# TECLADO-G5-5A_schDoc.net
KiCad netlist of a schematic drawn in Altium Designer
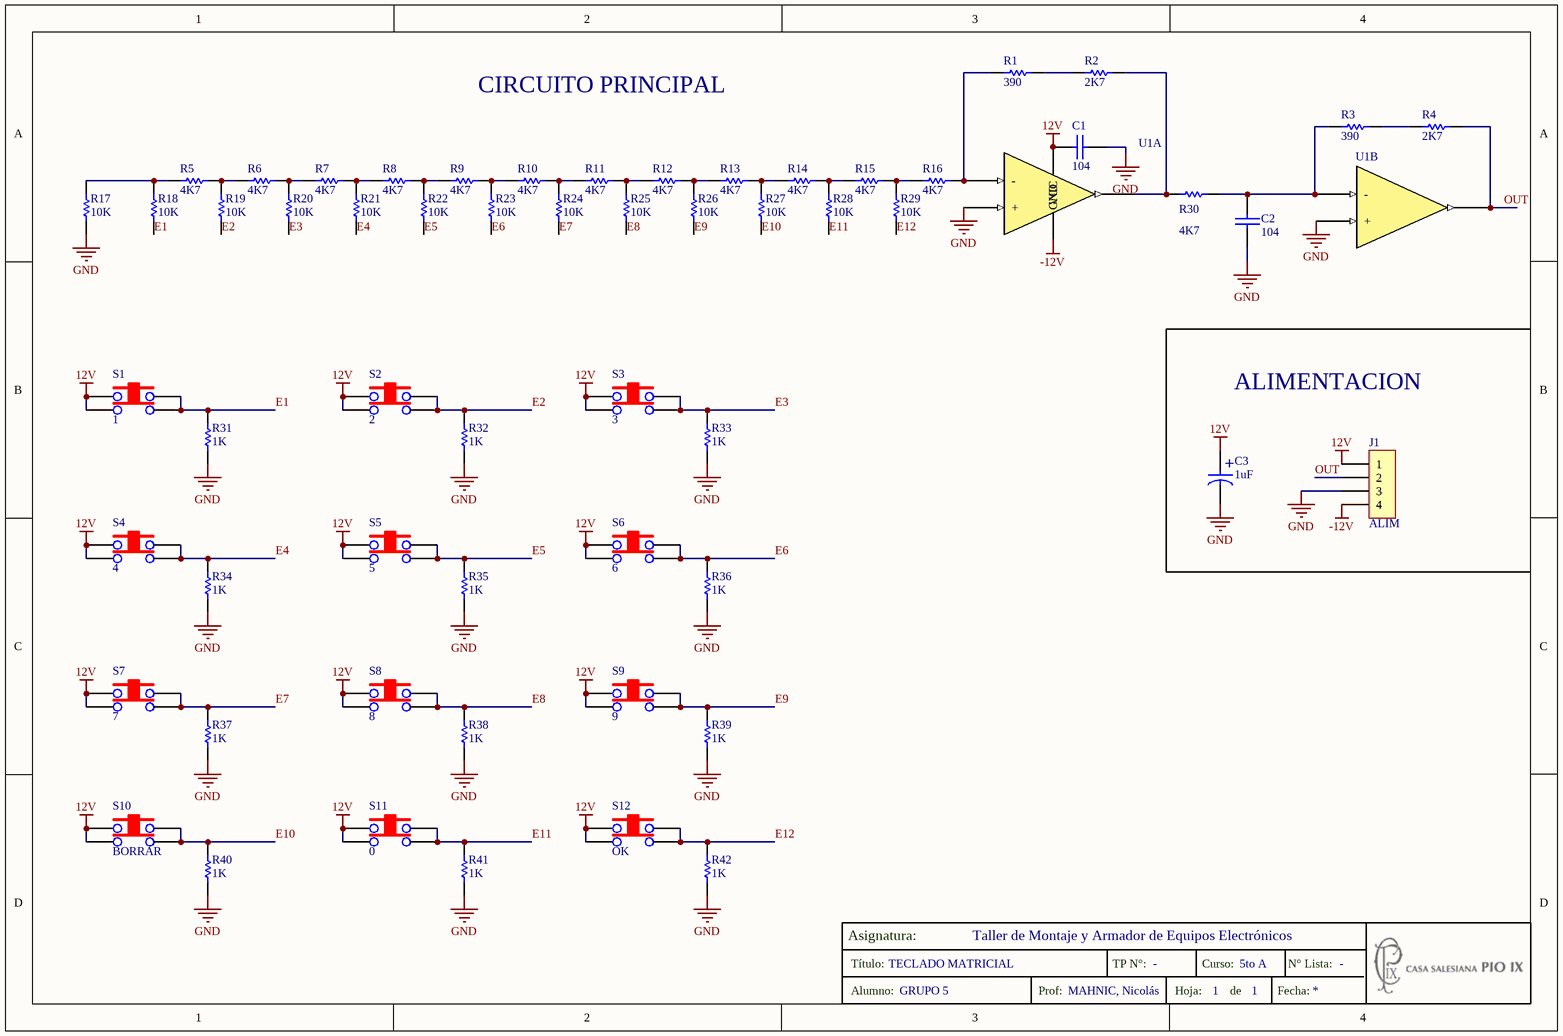
[diagram p0: TECLADO-G5-5A.schDoc.SchDoc]

(export (version "E")
  (design (tool "Eeschema 10.0.6"))
  (components
    (comp (ref "C1")
      (value "104")
      (footprint "0805")
      (description "Diodo 0805")
      (libsource (lib "Schlib1") (part "CAP"))
    )
    (comp (ref "C2")
      (value "104")
      (footprint "0805")
      (description "Diodo 0805")
      (libsource (lib "Schlib1") (part "CAP"))
    )
    (comp (ref "C3")
      (value "1uF")
      (footprint "Capol")
      (description "Cap polarizado")
      (libsource (lib "Schlib1") (part "CAPPOL"))
    )
    (comp (ref "J1") (value "ALIM") (footprint "SIP4") (libsource (lib "Schlib1") (part "CON4")))
    (comp (ref "R1")
      (value "390")
      (footprint "0805")
      (description "Resistencia")
      (libsource (lib "Schlib1") (part "RES"))
    )
    (comp (ref "R2")
      (value "2K7")
      (footprint "0805")
      (description "Resistencia")
      (libsource (lib "Schlib1") (part "RES"))
    )
    (comp (ref "R3")
      (value "390")
      (footprint "0805")
      (description "Resistencia")
      (libsource (lib "Schlib1") (part "RES"))
    )
    (comp (ref "R4")
      (value "2K7")
      (footprint "0805")
      (description "Resistencia")
      (libsource (lib "Schlib1") (part "RES"))
    )
    (comp (ref "R5")
      (value "4K7")
      (footprint "0805")
      (description "Resistencia")
      (libsource (lib "Schlib1") (part "RES"))
    )
    (comp (ref "R6")
      (value "4K7")
      (footprint "0805")
      (description "Resistencia")
      (libsource (lib "Schlib1") (part "RES"))
    )
    (comp (ref "R7")
      (value "4K7")
      (footprint "0805")
      (description "Resistencia")
      (libsource (lib "Schlib1") (part "RES"))
    )
    (comp (ref "R8")
      (value "4K7")
      (footprint "0805")
      (description "Resistencia")
      (libsource (lib "Schlib1") (part "RES"))
    )
    (comp (ref "R9")
      (value "4K7")
      (footprint "0805")
      (description "Resistencia")
      (libsource (lib "Schlib1") (part "RES"))
    )
    (comp (ref "R10")
      (value "4K7")
      (footprint "0805")
      (description "Resistencia")
      (libsource (lib "Schlib1") (part "RES"))
    )
    (comp (ref "R11")
      (value "4K7")
      (footprint "0805")
      (description "Resistencia")
      (libsource (lib "Schlib1") (part "RES"))
    )
    (comp (ref "R12")
      (value "4K7")
      (footprint "0805")
      (description "Resistencia")
      (libsource (lib "Schlib1") (part "RES"))
    )
    (comp (ref "R13")
      (value "4K7")
      (footprint "0805")
      (description "Resistencia")
      (libsource (lib "Schlib1") (part "RES"))
    )
    (comp (ref "R14")
      (value "4K7")
      (footprint "0805")
      (description "Resistencia")
      (libsource (lib "Schlib1") (part "RES"))
    )
    (comp (ref "R15")
      (value "4K7")
      (footprint "0805")
      (description "Resistencia")
      (libsource (lib "Schlib1") (part "RES"))
    )
    (comp (ref "R16")
      (value "4K7")
      (footprint "0805")
      (description "Resistencia")
      (libsource (lib "Schlib1") (part "RES"))
    )
    (comp (ref "R17")
      (value "10K")
      (footprint "0805")
      (description "Resistencia")
      (libsource (lib "Schlib1") (part "RES"))
    )
    (comp (ref "R18")
      (value "10K")
      (footprint "0805")
      (description "Resistencia")
      (libsource (lib "Schlib1") (part "RES"))
    )
    (comp (ref "R19")
      (value "10K")
      (footprint "0805")
      (description "Resistencia")
      (libsource (lib "Schlib1") (part "RES"))
    )
    (comp (ref "R20")
      (value "10K")
      (footprint "0805")
      (description "Resistencia")
      (libsource (lib "Schlib1") (part "RES"))
    )
    (comp (ref "R21")
      (value "10K")
      (footprint "0805")
      (description "Resistencia")
      (libsource (lib "Schlib1") (part "RES"))
    )
    (comp (ref "R22")
      (value "10K")
      (footprint "0805")
      (description "Resistencia")
      (libsource (lib "Schlib1") (part "RES"))
    )
    (comp (ref "R23")
      (value "10K")
      (footprint "0805")
      (description "Resistencia")
      (libsource (lib "Schlib1") (part "RES"))
    )
    (comp (ref "R24")
      (value "10K")
      (footprint "0805")
      (description "Resistencia")
      (libsource (lib "Schlib1") (part "RES"))
    )
    (comp (ref "R25")
      (value "10K")
      (footprint "0805")
      (description "Resistencia")
      (libsource (lib "Schlib1") (part "RES"))
    )
    (comp (ref "R26")
      (value "10K")
      (footprint "0805")
      (description "Resistencia")
      (libsource (lib "Schlib1") (part "RES"))
    )
    (comp (ref "R27")
      (value "10K")
      (footprint "0805")
      (description "Resistencia")
      (libsource (lib "Schlib1") (part "RES"))
    )
    (comp (ref "R28")
      (value "10K")
      (footprint "0805")
      (description "Resistencia")
      (libsource (lib "Schlib1") (part "RES"))
    )
    (comp (ref "R29")
      (value "10K")
      (footprint "0805")
      (description "Resistencia")
      (libsource (lib "Schlib1") (part "RES"))
    )
    (comp (ref "R30")
      (value "4K7")
      (footprint "0805")
      (description "Resistencia")
      (libsource (lib "Schlib1") (part "RES"))
    )
    (comp (ref "R31")
      (value "1K")
      (footprint "0805")
      (description "Resistencia")
      (libsource (lib "Schlib1") (part "RES"))
    )
    (comp (ref "R32")
      (value "1K")
      (footprint "0805")
      (description "Resistencia")
      (libsource (lib "Schlib1") (part "RES"))
    )
    (comp (ref "R33")
      (value "1K")
      (footprint "0805")
      (description "Resistencia")
      (libsource (lib "Schlib1") (part "RES"))
    )
    (comp (ref "R34")
      (value "1K")
      (footprint "0805")
      (description "Resistencia")
      (libsource (lib "Schlib1") (part "RES"))
    )
    (comp (ref "R35")
      (value "1K")
      (footprint "0805")
      (description "Resistencia")
      (libsource (lib "Schlib1") (part "RES"))
    )
    (comp (ref "R36")
      (value "1K")
      (footprint "0805")
      (description "Resistencia")
      (libsource (lib "Schlib1") (part "RES"))
    )
    (comp (ref "R37")
      (value "1K")
      (footprint "0805")
      (description "Resistencia")
      (libsource (lib "Schlib1") (part "RES"))
    )
    (comp (ref "R38")
      (value "1K")
      (footprint "0805")
      (description "Resistencia")
      (libsource (lib "Schlib1") (part "RES"))
    )
    (comp (ref "R39")
      (value "1K")
      (footprint "0805")
      (description "Resistencia")
      (libsource (lib "Schlib1") (part "RES"))
    )
    (comp (ref "R40")
      (value "1K")
      (footprint "0805")
      (description "Resistencia")
      (libsource (lib "Schlib1") (part "RES"))
    )
    (comp (ref "R41")
      (value "1K")
      (footprint "0805")
      (description "Resistencia")
      (libsource (lib "Schlib1") (part "RES"))
    )
    (comp (ref "R42")
      (value "1K")
      (footprint "0805")
      (description "Resistencia")
      (libsource (lib "Schlib1") (part "RES"))
    )
    (comp (ref "S1")
      (value "1")
      (footprint "pul_grande")
      (description "Pulsador")
      (fields (field (name "AUTOR") "Guido Spataro"))
      (libsource (lib "Schlib1") (part "Pulsador"))
    )
    (comp (ref "S2")
      (value "2")
      (footprint "pul_grande")
      (description "Pulsador")
      (fields (field (name "AUTOR") "Guido Spataro"))
      (libsource (lib "Schlib1") (part "Pulsador"))
    )
    (comp (ref "S3")
      (value "3")
      (footprint "pul_grande")
      (description "Pulsador")
      (fields (field (name "AUTOR") "Guido Spataro"))
      (libsource (lib "Schlib1") (part "Pulsador"))
    )
    (comp (ref "S4")
      (value "4")
      (footprint "pul_grande")
      (description "Pulsador")
      (fields (field (name "AUTOR") "Guido Spataro"))
      (libsource (lib "Schlib1") (part "Pulsador"))
    )
    (comp (ref "S5")
      (value "5")
      (footprint "pul_grande")
      (description "Pulsador")
      (fields (field (name "AUTOR") "Guido Spataro"))
      (libsource (lib "Schlib1") (part "Pulsador"))
    )
    (comp (ref "S6")
      (value "6")
      (footprint "pul_grande")
      (description "Pulsador")
      (fields (field (name "AUTOR") "Guido Spataro"))
      (libsource (lib "Schlib1") (part "Pulsador"))
    )
    (comp (ref "S7")
      (value "7")
      (footprint "pul_grande")
      (description "Pulsador")
      (fields (field (name "AUTOR") "Guido Spataro"))
      (libsource (lib "Schlib1") (part "Pulsador"))
    )
    (comp (ref "S8")
      (value "8")
      (footprint "pul_grande")
      (description "Pulsador")
      (fields (field (name "AUTOR") "Guido Spataro"))
      (libsource (lib "Schlib1") (part "Pulsador"))
    )
    (comp (ref "S9")
      (value "9")
      (footprint "pul_grande")
      (description "Pulsador")
      (fields (field (name "AUTOR") "Guido Spataro"))
      (libsource (lib "Schlib1") (part "Pulsador"))
    )
    (comp (ref "S10")
      (value "BORRAR")
      (footprint "pul_grande")
      (description "Pulsador")
      (fields (field (name "AUTOR") "Guido Spataro"))
      (libsource (lib "Schlib1") (part "Pulsador"))
    )
    (comp (ref "S11")
      (value "0")
      (footprint "pul_grande")
      (description "Pulsador")
      (fields (field (name "AUTOR") "Guido Spataro"))
      (libsource (lib "Schlib1") (part "Pulsador"))
    )
    (comp (ref "S12")
      (value "OK")
      (footprint "pul_grande")
      (description "Pulsador")
      (fields (field (name "AUTOR") "Guido Spataro"))
      (libsource (lib "Schlib1") (part "Pulsador"))
    )
    (comp (ref "U1") (value "~") (footprint "LM358 SMD") (libsource (lib "Schlib1") (part "LM358")))
  )
  (nets
    (net (code "1") (name "-12V") (class "Default")
      (node (ref "J1") (pin "4") (pinfunction "4_4") (pintype "passive"))
      (node (ref "U1") (pin "4") (pinfunction "GND_4") (pintype "passive"))
    )
    (net (code "2") (name "/E1") (class "Default")
      (node (ref "R18") (pin "1") (pinfunction "1_1") (pintype "passive"))
      (node (ref "R31") (pin "2") (pinfunction "2_2") (pintype "passive"))
      (node (ref "S1") (pin "3") (pinfunction "3_3") (pintype "passive"))
      (node (ref "S1") (pin "4") (pinfunction "4_4") (pintype "passive"))
    )
    (net (code "3") (name "/E2") (class "Default")
      (node (ref "R19") (pin "1") (pinfunction "1_1") (pintype "passive"))
      (node (ref "R32") (pin "2") (pinfunction "2_2") (pintype "passive"))
      (node (ref "S2") (pin "3") (pinfunction "3_3") (pintype "passive"))
      (node (ref "S2") (pin "4") (pinfunction "4_4") (pintype "passive"))
    )
    (net (code "4") (name "/E3") (class "Default")
      (node (ref "R20") (pin "1") (pinfunction "1_1") (pintype "passive"))
      (node (ref "R33") (pin "2") (pinfunction "2_2") (pintype "passive"))
      (node (ref "S3") (pin "3") (pinfunction "3_3") (pintype "passive"))
      (node (ref "S3") (pin "4") (pinfunction "4_4") (pintype "passive"))
    )
    (net (code "5") (name "/E4") (class "Default")
      (node (ref "R21") (pin "1") (pinfunction "1_1") (pintype "passive"))
      (node (ref "R34") (pin "2") (pinfunction "2_2") (pintype "passive"))
      (node (ref "S4") (pin "3") (pinfunction "3_3") (pintype "passive"))
      (node (ref "S4") (pin "4") (pinfunction "4_4") (pintype "passive"))
    )
    (net (code "6") (name "/E5") (class "Default")
      (node (ref "R22") (pin "1") (pinfunction "1_1") (pintype "passive"))
      (node (ref "R35") (pin "2") (pinfunction "2_2") (pintype "passive"))
      (node (ref "S5") (pin "3") (pinfunction "3_3") (pintype "passive"))
      (node (ref "S5") (pin "4") (pinfunction "4_4") (pintype "passive"))
    )
    (net (code "7") (name "/E6") (class "Default")
      (node (ref "R23") (pin "1") (pinfunction "1_1") (pintype "passive"))
      (node (ref "R36") (pin "2") (pinfunction "2_2") (pintype "passive"))
      (node (ref "S6") (pin "3") (pinfunction "3_3") (pintype "passive"))
      (node (ref "S6") (pin "4") (pinfunction "4_4") (pintype "passive"))
    )
    (net (code "8") (name "/E7") (class "Default")
      (node (ref "R24") (pin "1") (pinfunction "1_1") (pintype "passive"))
      (node (ref "R37") (pin "2") (pinfunction "2_2") (pintype "passive"))
      (node (ref "S7") (pin "3") (pinfunction "3_3") (pintype "passive"))
      (node (ref "S7") (pin "4") (pinfunction "4_4") (pintype "passive"))
    )
    (net (code "9") (name "/E8") (class "Default")
      (node (ref "R25") (pin "1") (pinfunction "1_1") (pintype "passive"))
      (node (ref "R38") (pin "2") (pinfunction "2_2") (pintype "passive"))
      (node (ref "S8") (pin "3") (pinfunction "3_3") (pintype "passive"))
      (node (ref "S8") (pin "4") (pinfunction "4_4") (pintype "passive"))
    )
    (net (code "10") (name "/E9") (class "Default")
      (node (ref "R26") (pin "1") (pinfunction "1_1") (pintype "passive"))
      (node (ref "R39") (pin "2") (pinfunction "2_2") (pintype "passive"))
      (node (ref "S9") (pin "3") (pinfunction "3_3") (pintype "passive"))
      (node (ref "S9") (pin "4") (pinfunction "4_4") (pintype "passive"))
    )
    (net (code "11") (name "/E10") (class "Default")
      (node (ref "R27") (pin "1") (pinfunction "1_1") (pintype "passive"))
      (node (ref "R40") (pin "2") (pinfunction "2_2") (pintype "passive"))
      (node (ref "S10") (pin "3") (pinfunction "3_3") (pintype "passive"))
      (node (ref "S10") (pin "4") (pinfunction "4_4") (pintype "passive"))
    )
    (net (code "12") (name "/E11") (class "Default")
      (node (ref "R28") (pin "1") (pinfunction "1_1") (pintype "passive"))
      (node (ref "R41") (pin "2") (pinfunction "2_2") (pintype "passive"))
      (node (ref "S11") (pin "3") (pinfunction "3_3") (pintype "passive"))
      (node (ref "S11") (pin "4") (pinfunction "4_4") (pintype "passive"))
    )
    (net (code "13") (name "/E12") (class "Default")
      (node (ref "R29") (pin "1") (pinfunction "1_1") (pintype "passive"))
      (node (ref "R42") (pin "2") (pinfunction "2_2") (pintype "passive"))
      (node (ref "S12") (pin "3") (pinfunction "3_3") (pintype "passive"))
      (node (ref "S12") (pin "4") (pinfunction "4_4") (pintype "passive"))
    )
    (net (code "14") (name "/OUT") (class "Default")
      (node (ref "J1") (pin "2") (pinfunction "2_2") (pintype "passive"))
      (node (ref "R4") (pin "1") (pinfunction "1_1") (pintype "passive"))
      (node (ref "U1") (pin "7") (pinfunction "OUT_B_7") (pintype "output"))
    )
    (net (code "15") (name "12V") (class "Default")
      (node (ref "C1") (pin "1") (pinfunction "1_1") (pintype "passive"))
      (node (ref "C3") (pin "1") (pinfunction "1_1") (pintype "passive"))
      (node (ref "J1") (pin "1") (pinfunction "1_1") (pintype "passive"))
      (node (ref "S1") (pin "1") (pinfunction "1_1") (pintype "passive"))
      (node (ref "S1") (pin "2") (pinfunction "2_2") (pintype "passive"))
      (node (ref "S10") (pin "1") (pinfunction "1_1") (pintype "passive"))
      (node (ref "S10") (pin "2") (pinfunction "2_2") (pintype "passive"))
      (node (ref "S11") (pin "1") (pinfunction "1_1") (pintype "passive"))
      (node (ref "S11") (pin "2") (pinfunction "2_2") (pintype "passive"))
      (node (ref "S12") (pin "1") (pinfunction "1_1") (pintype "passive"))
      (node (ref "S12") (pin "2") (pinfunction "2_2") (pintype "passive"))
      (node (ref "S2") (pin "1") (pinfunction "1_1") (pintype "passive"))
      (node (ref "S2") (pin "2") (pinfunction "2_2") (pintype "passive"))
      (node (ref "S3") (pin "1") (pinfunction "1_1") (pintype "passive"))
      (node (ref "S3") (pin "2") (pinfunction "2_2") (pintype "passive"))
      (node (ref "S4") (pin "1") (pinfunction "1_1") (pintype "passive"))
      (node (ref "S4") (pin "2") (pinfunction "2_2") (pintype "passive"))
      (node (ref "S5") (pin "1") (pinfunction "1_1") (pintype "passive"))
      (node (ref "S5") (pin "2") (pinfunction "2_2") (pintype "passive"))
      (node (ref "S6") (pin "1") (pinfunction "1_1") (pintype "passive"))
      (node (ref "S6") (pin "2") (pinfunction "2_2") (pintype "passive"))
      (node (ref "S7") (pin "1") (pinfunction "1_1") (pintype "passive"))
      (node (ref "S7") (pin "2") (pinfunction "2_2") (pintype "passive"))
      (node (ref "S8") (pin "1") (pinfunction "1_1") (pintype "passive"))
      (node (ref "S8") (pin "2") (pinfunction "2_2") (pintype "passive"))
      (node (ref "S9") (pin "1") (pinfunction "1_1") (pintype "passive"))
      (node (ref "S9") (pin "2") (pinfunction "2_2") (pintype "passive"))
      (node (ref "U1") (pin "8") (pinfunction "VCC_8") (pintype "passive"))
    )
    (net (code "16") (name "GND") (class "Default")
      (node (ref "C1") (pin "2") (pinfunction "2_2") (pintype "passive"))
      (node (ref "C2") (pin "2") (pinfunction "2_2") (pintype "passive"))
      (node (ref "C3") (pin "2") (pinfunction "2_2") (pintype "passive"))
      (node (ref "J1") (pin "3") (pinfunction "3_3") (pintype "passive"))
      (node (ref "R17") (pin "1") (pinfunction "1_1") (pintype "passive"))
      (node (ref "R31") (pin "1") (pinfunction "1_1") (pintype "passive"))
      (node (ref "R32") (pin "1") (pinfunction "1_1") (pintype "passive"))
      (node (ref "R33") (pin "1") (pinfunction "1_1") (pintype "passive"))
      (node (ref "R34") (pin "1") (pinfunction "1_1") (pintype "passive"))
      (node (ref "R35") (pin "1") (pinfunction "1_1") (pintype "passive"))
      (node (ref "R36") (pin "1") (pinfunction "1_1") (pintype "passive"))
      (node (ref "R37") (pin "1") (pinfunction "1_1") (pintype "passive"))
      (node (ref "R38") (pin "1") (pinfunction "1_1") (pintype "passive"))
      (node (ref "R39") (pin "1") (pinfunction "1_1") (pintype "passive"))
      (node (ref "R40") (pin "1") (pinfunction "1_1") (pintype "passive"))
      (node (ref "R41") (pin "1") (pinfunction "1_1") (pintype "passive"))
      (node (ref "R42") (pin "1") (pinfunction "1_1") (pintype "passive"))
      (node (ref "U1") (pin "3") (pinfunction "+_3") (pintype "input"))
      (node (ref "U1") (pin "5") (pinfunction "+_5") (pintype "input"))
    )
    (net (code "17") (name "Net-(R1-Pad1)") (class "Default")
      (node (ref "R1") (pin "1") (pinfunction "1_1") (pintype "passive"))
      (node (ref "R2") (pin "2") (pinfunction "2_2") (pintype "passive"))
    )
    (net (code "18") (name "Net-(R3-Pad1)") (class "Default")
      (node (ref "R3") (pin "1") (pinfunction "1_1") (pintype "passive"))
      (node (ref "R4") (pin "2") (pinfunction "2_2") (pintype "passive"))
    )
    (net (code "19") (name "Net-(R10-Pad1)") (class "Default")
      (node (ref "R10") (pin "1") (pinfunction "1_1") (pintype "passive"))
      (node (ref "R11") (pin "2") (pinfunction "2_2") (pintype "passive"))
      (node (ref "R24") (pin "2") (pinfunction "2_2") (pintype "passive"))
    )
    (net (code "20") (name "Net-(R10-Pad2)") (class "Default")
      (node (ref "R10") (pin "2") (pinfunction "2_2") (pintype "passive"))
      (node (ref "R23") (pin "2") (pinfunction "2_2") (pintype "passive"))
      (node (ref "R9") (pin "1") (pinfunction "1_1") (pintype "passive"))
    )
    (net (code "21") (name "Net-(R11-Pad1)") (class "Default")
      (node (ref "R11") (pin "1") (pinfunction "1_1") (pintype "passive"))
      (node (ref "R12") (pin "2") (pinfunction "2_2") (pintype "passive"))
      (node (ref "R25") (pin "2") (pinfunction "2_2") (pintype "passive"))
    )
    (net (code "22") (name "Net-(R12-Pad1)") (class "Default")
      (node (ref "R12") (pin "1") (pinfunction "1_1") (pintype "passive"))
      (node (ref "R13") (pin "2") (pinfunction "2_2") (pintype "passive"))
      (node (ref "R26") (pin "2") (pinfunction "2_2") (pintype "passive"))
    )
    (net (code "23") (name "Net-(R13-Pad1)") (class "Default")
      (node (ref "R13") (pin "1") (pinfunction "1_1") (pintype "passive"))
      (node (ref "R14") (pin "2") (pinfunction "2_2") (pintype "passive"))
      (node (ref "R27") (pin "2") (pinfunction "2_2") (pintype "passive"))
    )
    (net (code "24") (name "Net-(R14-Pad1)") (class "Default")
      (node (ref "R14") (pin "1") (pinfunction "1_1") (pintype "passive"))
      (node (ref "R15") (pin "2") (pinfunction "2_2") (pintype "passive"))
      (node (ref "R28") (pin "2") (pinfunction "2_2") (pintype "passive"))
    )
    (net (code "25") (name "Net-(R15-Pad1)") (class "Default")
      (node (ref "R15") (pin "1") (pinfunction "1_1") (pintype "passive"))
      (node (ref "R16") (pin "2") (pinfunction "2_2") (pintype "passive"))
      (node (ref "R29") (pin "2") (pinfunction "2_2") (pintype "passive"))
    )
    (net (code "26") (name "Net-(R17-Pad2)") (class "Default")
      (node (ref "R17") (pin "2") (pinfunction "2_2") (pintype "passive"))
      (node (ref "R18") (pin "2") (pinfunction "2_2") (pintype "passive"))
      (node (ref "R5") (pin "2") (pinfunction "2_2") (pintype "passive"))
    )
    (net (code "27") (name "Net-(R19-Pad2)") (class "Default")
      (node (ref "R19") (pin "2") (pinfunction "2_2") (pintype "passive"))
      (node (ref "R5") (pin "1") (pinfunction "1_1") (pintype "passive"))
      (node (ref "R6") (pin "2") (pinfunction "2_2") (pintype "passive"))
    )
    (net (code "28") (name "Net-(R20-Pad2)") (class "Default")
      (node (ref "R20") (pin "2") (pinfunction "2_2") (pintype "passive"))
      (node (ref "R6") (pin "1") (pinfunction "1_1") (pintype "passive"))
      (node (ref "R7") (pin "2") (pinfunction "2_2") (pintype "passive"))
    )
    (net (code "29") (name "Net-(R21-Pad2)") (class "Default")
      (node (ref "R21") (pin "2") (pinfunction "2_2") (pintype "passive"))
      (node (ref "R7") (pin "1") (pinfunction "1_1") (pintype "passive"))
      (node (ref "R8") (pin "2") (pinfunction "2_2") (pintype "passive"))
    )
    (net (code "30") (name "Net-(R22-Pad2)") (class "Default")
      (node (ref "R22") (pin "2") (pinfunction "2_2") (pintype "passive"))
      (node (ref "R8") (pin "1") (pinfunction "1_1") (pintype "passive"))
      (node (ref "R9") (pin "2") (pinfunction "2_2") (pintype "passive"))
    )
    (net (code "31") (name "Net-(U1A--)") (class "Default")
      (node (ref "R1") (pin "2") (pinfunction "2_2") (pintype "passive"))
      (node (ref "R16") (pin "1") (pinfunction "1_1") (pintype "passive"))
      (node (ref "U1") (pin "2") (pinfunction "-_2") (pintype "input"))
    )
    (net (code "32") (name "Net-(U1A-OUT_A)") (class "Default")
      (node (ref "R2") (pin "1") (pinfunction "1_1") (pintype "passive"))
      (node (ref "R30") (pin "2") (pinfunction "2_2") (pintype "passive"))
      (node (ref "U1") (pin "1") (pinfunction "OUT_A_1") (pintype "output"))
    )
    (net (code "33") (name "Net-(U1B--)") (class "Default")
      (node (ref "C2") (pin "1") (pinfunction "1_1") (pintype "passive"))
      (node (ref "R3") (pin "2") (pinfunction "2_2") (pintype "passive"))
      (node (ref "R30") (pin "1") (pinfunction "1_1") (pintype "passive"))
      (node (ref "U1") (pin "6") (pinfunction "-_6") (pintype "input"))
    )
  )
)
